# CM0_Controller.net
KiCad netlist of a schematic drawn in Altium Designer
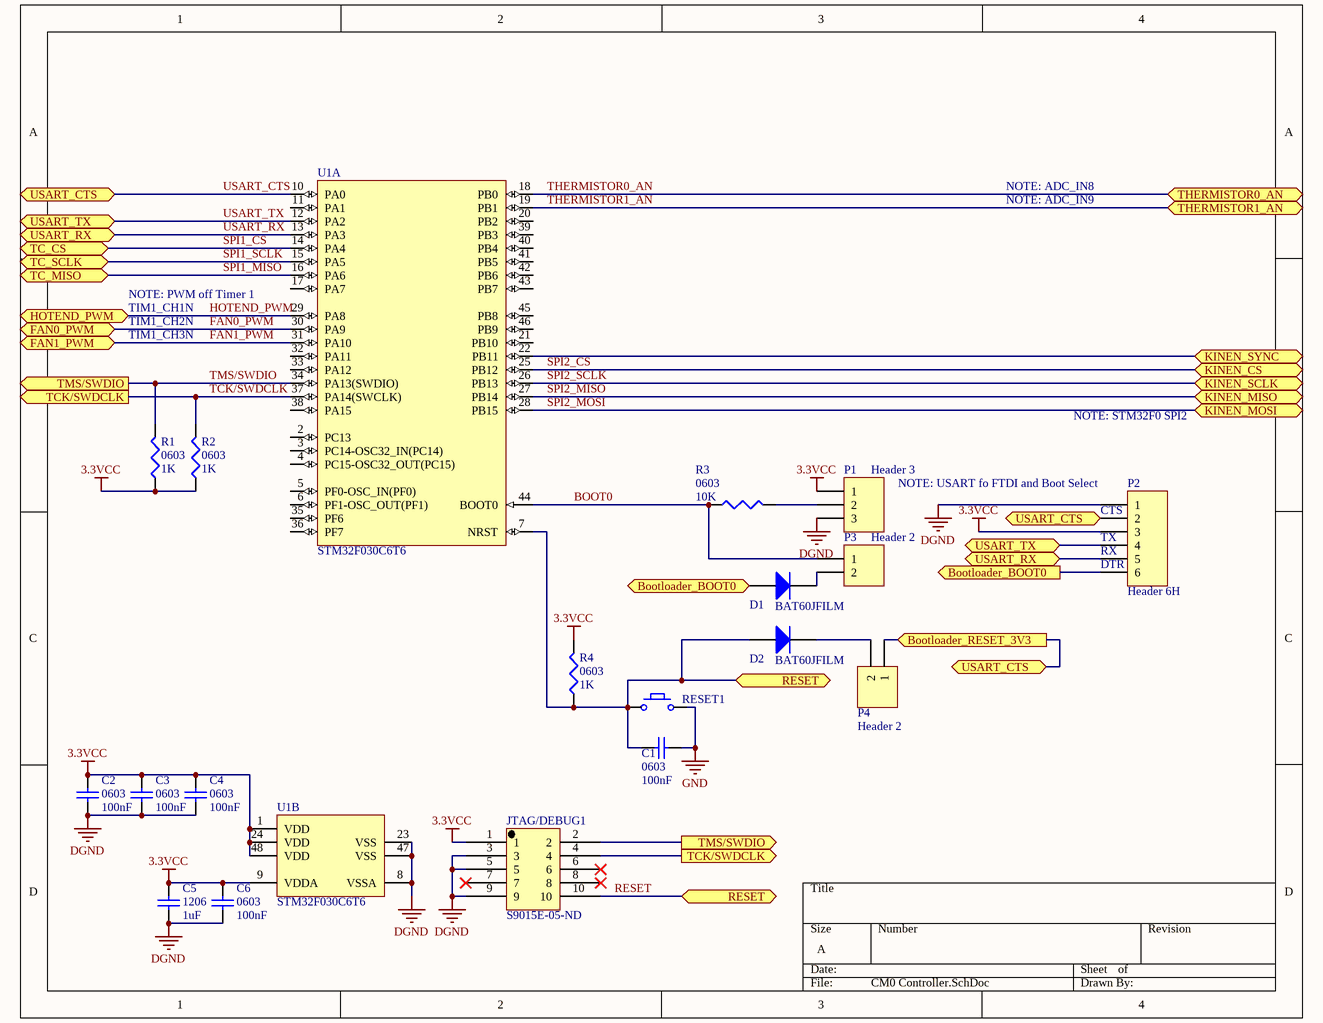
[diagram p0: CM0 Controller.SchDoc]

(export (version "E")
  (design (tool "Eeschema 10.0.6"))
  (components
    (comp (ref "C1")
      (value "0603")
      (footprint "1608[0603]")
      (description "Capacitor (Semiconductor SIM Model)")
      (fields (field (name "ALTIUM_VALUE") "100nF") (field (name "PUBLISHER") "Altium Limited"))
      (libsource (lib "Miscellaneous Devices") (part "Cap Semi"))
    )
    (comp (ref "C2")
      (value "0603")
      (footprint "1608[0603]")
      (description "Capacitor (Semiconductor SIM Model)")
      (fields (field (name "ALTIUM_VALUE") "100nF") (field (name "PUBLISHER") "Altium Limited"))
      (libsource (lib "Miscellaneous Devices") (part "Cap Semi"))
    )
    (comp (ref "C3")
      (value "0603")
      (footprint "1608[0603]")
      (description "Capacitor (Semiconductor SIM Model)")
      (fields (field (name "ALTIUM_VALUE") "100nF") (field (name "PUBLISHER") "Altium Limited"))
      (libsource (lib "Miscellaneous Devices") (part "Cap Semi"))
    )
    (comp (ref "C4")
      (value "0603")
      (footprint "1608[0603]")
      (description "Capacitor (Semiconductor SIM Model)")
      (fields (field (name "ALTIUM_VALUE") "100nF") (field (name "PUBLISHER") "Altium Limited"))
      (libsource (lib "Miscellaneous Devices") (part "Cap Semi"))
    )
    (comp (ref "C5")
      (value "1206")
      (footprint "C1206")
      (description "Capacitor (Semiconductor SIM Model)")
      (fields (field (name "ALTIUM_VALUE") "1uF") (field (name "PUBLISHER") "Altium Limited"))
      (libsource (lib "Miscellaneous Devices") (part "Cap Semi"))
    )
    (comp (ref "C6")
      (value "0603")
      (footprint "1608[0603]")
      (description "Capacitor (Semiconductor SIM Model)")
      (fields (field (name "ALTIUM_VALUE") "100nF") (field (name "PUBLISHER") "Altium Limited"))
      (libsource (lib "Miscellaneous Devices") (part "Cap Semi"))
    )
    (comp (ref "D1")
      (value "BAT60JFILM")
      (footprint "SOD-323")
      (description "Default Diode")
      (fields (field (name "PUBLISHER") "Altium Limited"))
      (libsource (lib "Miscellaneous Devices") (part "Diode"))
    )
    (comp (ref "D2")
      (value "BAT60JFILM")
      (footprint "SOD-323")
      (description "Default Diode")
      (fields (field (name "PUBLISHER") "Altium Limited"))
      (libsource (lib "Miscellaneous Devices") (part "Diode"))
    )
    (comp (ref "JTAG/DEBUG1")
      (value "S9015E-05-ND")
      (footprint "S9015E-05-ND")
      (libsource (lib "Adams Altium Library") (part "S9015E-05-ND"))
    )
    (comp (ref "P1")
      (value "Header 3")
      (footprint "HDR1X3")
      (description "Header, 3-Pin")
      (fields (field (name "PUBLISHER") "Altium Limited"))
      (libsource (lib "Miscellaneous Connectors") (part "Header 3"))
    )
    (comp (ref "P2")
      (value "Header 6H")
      (footprint "HDR1X6H")
      (description "Header, 6-Pin, Right Angle")
      (fields (field (name "PUBLISHER") "Altium Limited"))
      (libsource (lib "Miscellaneous Connectors") (part "Header 6H"))
    )
    (comp (ref "P3")
      (value "Header 2")
      (footprint "HDR1X2")
      (description "Header, 2-Pin")
      (fields (field (name "PUBLISHER") "Altium Limited"))
      (libsource (lib "") (part "Header 2_1"))
    )
    (comp (ref "P4")
      (value "Header 2")
      (footprint "HDR1X2")
      (description "Header, 2-Pin")
      (fields (field (name "PUBLISHER") "Altium Limited"))
      (libsource (lib "Miscellaneous Connectors") (part "Header 2"))
    )
    (comp (ref "R1")
      (value "0603")
      (footprint "J1-0603")
      (description "Resistor")
      (fields (field (name "ALTIUM_VALUE") "1K") (field (name "PUBLISHER") "Altium Limited"))
      (libsource (lib "Miscellaneous Devices") (part "Res3"))
    )
    (comp (ref "R2")
      (value "0603")
      (footprint "J1-0603")
      (description "Resistor")
      (fields (field (name "ALTIUM_VALUE") "1K") (field (name "PUBLISHER") "Altium Limited"))
      (libsource (lib "Miscellaneous Devices") (part "Res3"))
    )
    (comp (ref "R3")
      (value "0603")
      (footprint "J1-0603")
      (description "Resistor")
      (fields (field (name "ALTIUM_VALUE") "10K") (field (name "PUBLISHER") "Altium Limited"))
      (libsource (lib "Miscellaneous Devices") (part "Res3"))
    )
    (comp (ref "R4")
      (value "0603")
      (footprint "J1-0603")
      (description "Resistor")
      (fields (field (name "ALTIUM_VALUE") "1K") (field (name "PUBLISHER") "Altium Limited"))
      (libsource (lib "Miscellaneous Devices") (part "Res3"))
    )
    (comp (ref "RESET1")
      (value "Tactile Switch")
      (footprint "tactile switch")
      (libsource (lib "Adams Altium Library") (part "Tactile Switch"))
    )
    (comp (ref "U1")
      (value "STM32F030C6T6")
      (footprint "STM-LQFP48_L")
      (libsource (lib "STMicroelectronics STM32 F0") (part "STM32F030C6T6"))
    )
  )
  (nets
    (net (code "1") (name "/BOOT0") (class "Default")
      (node (ref "P3") (pin "1") (pinfunction "1_1") (pintype "passive"))
      (node (ref "R3") (pin "1") (pinfunction "1_1") (pintype "passive"))
      (node (ref "U1") (pin "44") (pinfunction "BOOT0_44") (pintype "input"))
    )
    (net (code "2") (name "/Bootloader_BOOT0") (class "Default")
      (node (ref "D1") (pin "1") (pinfunction "A_1") (pintype "passive"))
      (node (ref "P2") (pin "6") (pinfunction "6_6") (pintype "passive"))
    )
    (net (code "3") (name "/FAN0_PWM") (class "Default")
      (node (ref "U1") (pin "30") (pinfunction "PA9_30") (pintype "bidirectional"))
    )
    (net (code "4") (name "/FAN1_PWM") (class "Default")
      (node (ref "U1") (pin "31") (pinfunction "PA10_31") (pintype "bidirectional"))
    )
    (net (code "5") (name "/HOTEND_PWM") (class "Default")
      (node (ref "U1") (pin "29") (pinfunction "PA8_29") (pintype "bidirectional"))
    )
    (net (code "6") (name "/KINEN_SYNC") (class "Default")
      (node (ref "U1") (pin "22") (pinfunction "PB11_22") (pintype "bidirectional"))
    )
    (net (code "7") (name "/RESET") (class "Default")
      (node (ref "C1") (pin "2") (pinfunction "2_2") (pintype "passive"))
      (node (ref "D2") (pin "1") (pinfunction "A_1") (pintype "passive"))
      (node (ref "JTAG/DEBUG1") (pin "10") (pinfunction "10_10") (pintype "passive"))
      (node (ref "R4") (pin "1") (pinfunction "1_1") (pintype "passive"))
      (node (ref "RESET1") (pin "1") (pintype "passive"))
      (node (ref "U1") (pin "7") (pinfunction "NRST_7") (pintype "bidirectional"))
    )
    (net (code "8") (name "/SPI1_CS") (class "Default")
      (node (ref "U1") (pin "14") (pinfunction "PA4_14") (pintype "bidirectional"))
    )
    (net (code "9") (name "/SPI1_MISO") (class "Default")
      (node (ref "U1") (pin "16") (pinfunction "PA6_16") (pintype "bidirectional"))
    )
    (net (code "10") (name "/SPI1_SCLK") (class "Default")
      (node (ref "U1") (pin "15") (pinfunction "PA5_15") (pintype "bidirectional"))
    )
    (net (code "11") (name "/SPI2_CS") (class "Default")
      (node (ref "U1") (pin "25") (pinfunction "PB12_25") (pintype "bidirectional"))
    )
    (net (code "12") (name "/SPI2_MISO") (class "Default")
      (node (ref "U1") (pin "27") (pinfunction "PB14_27") (pintype "bidirectional"))
    )
    (net (code "13") (name "/SPI2_MOSI") (class "Default")
      (node (ref "U1") (pin "28") (pinfunction "PB15_28") (pintype "bidirectional"))
    )
    (net (code "14") (name "/SPI2_SCLK") (class "Default")
      (node (ref "U1") (pin "26") (pinfunction "PB13_26") (pintype "bidirectional"))
    )
    (net (code "15") (name "/TCK{slash}SWDCLK") (class "Default")
      (node (ref "JTAG/DEBUG1") (pin "4") (pinfunction "4_4") (pintype "passive"))
      (node (ref "R2") (pin "2") (pinfunction "2_2") (pintype "passive"))
      (node (ref "U1") (pin "37") (pinfunction "PA14(SWCLK)_37") (pintype "bidirectional"))
    )
    (net (code "16") (name "/THERMISTOR0_AN") (class "Default")
      (node (ref "U1") (pin "18") (pinfunction "PB0_18") (pintype "bidirectional"))
    )
    (net (code "17") (name "/THERMISTOR1_AN") (class "Default")
      (node (ref "U1") (pin "19") (pinfunction "PB1_19") (pintype "bidirectional"))
    )
    (net (code "18") (name "/TMS{slash}SWDIO") (class "Default")
      (node (ref "JTAG/DEBUG1") (pin "2") (pinfunction "2_2") (pintype "passive"))
      (node (ref "R1") (pin "2") (pinfunction "2_2") (pintype "passive"))
      (node (ref "U1") (pin "34") (pinfunction "PA13(SWDIO)_34") (pintype "bidirectional"))
    )
    (net (code "19") (name "/USART_CTS") (class "Default")
      (node (ref "P2") (pin "2") (pinfunction "2_2") (pintype "passive"))
      (node (ref "P4") (pin "1") (pinfunction "1_1") (pintype "passive"))
      (node (ref "U1") (pin "10") (pinfunction "PA0_10") (pintype "bidirectional"))
    )
    (net (code "20") (name "/USART_RX") (class "Default")
      (node (ref "P2") (pin "5") (pinfunction "5_5") (pintype "passive"))
      (node (ref "U1") (pin "13") (pinfunction "PA3_13") (pintype "bidirectional"))
    )
    (net (code "21") (name "/USART_TX") (class "Default")
      (node (ref "P2") (pin "4") (pinfunction "4_4") (pintype "passive"))
      (node (ref "U1") (pin "12") (pinfunction "PA2_12") (pintype "bidirectional"))
    )
    (net (code "22") (name "3.3VCC") (class "Default")
      (node (ref "C2") (pin "2") (pinfunction "2_2") (pintype "passive"))
      (node (ref "C3") (pin "2") (pinfunction "2_2") (pintype "passive"))
      (node (ref "C4") (pin "2") (pinfunction "2_2") (pintype "passive"))
      (node (ref "C5") (pin "1") (pinfunction "1_1") (pintype "passive"))
      (node (ref "C6") (pin "1") (pinfunction "1_1") (pintype "passive"))
      (node (ref "JTAG/DEBUG1") (pin "1") (pinfunction "1_1") (pintype "passive"))
      (node (ref "P1") (pin "1") (pinfunction "1_1") (pintype "passive"))
      (node (ref "P2") (pin "3") (pinfunction "3_3") (pintype "passive"))
      (node (ref "R1") (pin "1") (pinfunction "1_1") (pintype "passive"))
      (node (ref "R2") (pin "1") (pinfunction "1_1") (pintype "passive"))
      (node (ref "R4") (pin "2") (pinfunction "2_2") (pintype "passive"))
      (node (ref "U1") (pin "1") (pinfunction "VDD_1") (pintype "power_in"))
      (node (ref "U1") (pin "24") (pinfunction "VDD_24") (pintype "power_in"))
      (node (ref "U1") (pin "48") (pinfunction "VDD_48") (pintype "power_in"))
      (node (ref "U1") (pin "9") (pinfunction "VDDA_9") (pintype "power_in"))
    )
    (net (code "23") (name "DGND") (class "Default")
      (node (ref "C2") (pin "1") (pinfunction "1_1") (pintype "passive"))
      (node (ref "C3") (pin "1") (pinfunction "1_1") (pintype "passive"))
      (node (ref "C4") (pin "1") (pinfunction "1_1") (pintype "passive"))
      (node (ref "C5") (pin "2") (pinfunction "2_2") (pintype "passive"))
      (node (ref "C6") (pin "2") (pinfunction "2_2") (pintype "passive"))
      (node (ref "JTAG/DEBUG1") (pin "3") (pinfunction "3_3") (pintype "passive"))
      (node (ref "JTAG/DEBUG1") (pin "5") (pinfunction "5_5") (pintype "passive"))
      (node (ref "JTAG/DEBUG1") (pin "9") (pinfunction "9_9") (pintype "passive"))
      (node (ref "P1") (pin "3") (pinfunction "3_3") (pintype "passive"))
      (node (ref "P2") (pin "1") (pinfunction "1_1") (pintype "passive"))
      (node (ref "U1") (pin "23") (pinfunction "VSS_23") (pintype "power_in"))
      (node (ref "U1") (pin "47") (pinfunction "VSS_47") (pintype "power_in"))
      (node (ref "U1") (pin "8") (pinfunction "VSSA_8") (pintype "power_in"))
    )
    (net (code "24") (name "GND") (class "Default")
      (node (ref "C1") (pin "1") (pinfunction "1_1") (pintype "passive"))
      (node (ref "RESET1") (pin "2") (pintype "passive"))
    )
    (net (code "25") (name "Net-(D1-K)") (class "Default")
      (node (ref "D1") (pin "2") (pinfunction "K_2") (pintype "passive"))
      (node (ref "P3") (pin "2") (pinfunction "2_2") (pintype "passive"))
    )
    (net (code "26") (name "Net-(D2-K)") (class "Default")
      (node (ref "D2") (pin "2") (pinfunction "K_2") (pintype "passive"))
      (node (ref "P4") (pin "2") (pinfunction "2_2") (pintype "passive"))
    )
    (net (code "27") (name "Net-(P1-Pad2)") (class "Default")
      (node (ref "P1") (pin "2") (pinfunction "2_2") (pintype "passive"))
      (node (ref "R3") (pin "2") (pinfunction "2_2") (pintype "passive"))
    )
    (net (code "28") (name "unconnected-(JTAG/DEBUG1-Pad6)") (class "Default")
      (node (ref "JTAG/DEBUG1") (pin "6") (pinfunction "6_6") (pintype "passive+no_connect"))
    )
    (net (code "29") (name "unconnected-(JTAG/DEBUG1-Pad7)") (class "Default")
      (node (ref "JTAG/DEBUG1") (pin "7") (pinfunction "7_7") (pintype "passive+no_connect"))
    )
    (net (code "30") (name "unconnected-(JTAG/DEBUG1-Pad8)") (class "Default")
      (node (ref "JTAG/DEBUG1") (pin "8") (pinfunction "8_8") (pintype "passive+no_connect"))
    )
    (net (code "31") (name "unconnected-(U1A-PA1-Pad11)") (class "Default")
      (node (ref "U1") (pin "11") (pinfunction "PA1_11") (pintype "bidirectional"))
    )
    (net (code "32") (name "unconnected-(U1A-PA7-Pad17)") (class "Default")
      (node (ref "U1") (pin "17") (pinfunction "PA7_17") (pintype "bidirectional"))
    )
    (net (code "33") (name "unconnected-(U1A-PA11-Pad32)") (class "Default")
      (node (ref "U1") (pin "32") (pinfunction "PA11_32") (pintype "bidirectional"))
    )
    (net (code "34") (name "unconnected-(U1A-PA12-Pad33)") (class "Default")
      (node (ref "U1") (pin "33") (pinfunction "PA12_33") (pintype "bidirectional"))
    )
    (net (code "35") (name "unconnected-(U1A-PA15-Pad38)") (class "Default")
      (node (ref "U1") (pin "38") (pinfunction "PA15_38") (pintype "bidirectional"))
    )
    (net (code "36") (name "unconnected-(U1A-PB2-Pad20)") (class "Default")
      (node (ref "U1") (pin "20") (pinfunction "PB2_20") (pintype "bidirectional"))
    )
    (net (code "37") (name "unconnected-(U1A-PB3-Pad39)") (class "Default")
      (node (ref "U1") (pin "39") (pinfunction "PB3_39") (pintype "bidirectional"))
    )
    (net (code "38") (name "unconnected-(U1A-PB4-Pad40)") (class "Default")
      (node (ref "U1") (pin "40") (pinfunction "PB4_40") (pintype "bidirectional"))
    )
    (net (code "39") (name "unconnected-(U1A-PB5-Pad41)") (class "Default")
      (node (ref "U1") (pin "41") (pinfunction "PB5_41") (pintype "bidirectional"))
    )
    (net (code "40") (name "unconnected-(U1A-PB6-Pad42)") (class "Default")
      (node (ref "U1") (pin "42") (pinfunction "PB6_42") (pintype "bidirectional"))
    )
    (net (code "41") (name "unconnected-(U1A-PB7-Pad43)") (class "Default")
      (node (ref "U1") (pin "43") (pinfunction "PB7_43") (pintype "bidirectional"))
    )
    (net (code "42") (name "unconnected-(U1A-PB8-Pad45)") (class "Default")
      (node (ref "U1") (pin "45") (pinfunction "PB8_45") (pintype "bidirectional"))
    )
    (net (code "43") (name "unconnected-(U1A-PB9-Pad46)") (class "Default")
      (node (ref "U1") (pin "46") (pinfunction "PB9_46") (pintype "bidirectional"))
    )
    (net (code "44") (name "unconnected-(U1A-PB10-Pad21)") (class "Default")
      (node (ref "U1") (pin "21") (pinfunction "PB10_21") (pintype "bidirectional"))
    )
    (net (code "45") (name "unconnected-(U1A-PC13-Pad2)") (class "Default")
      (node (ref "U1") (pin "2") (pinfunction "PC13_2") (pintype "bidirectional"))
    )
    (net (code "46") (name "unconnected-(U1A-PC14-OSC32_IN(PC14)-Pad3)") (class "Default")
      (node (ref "U1") (pin "3") (pinfunction "PC14-OSC32_IN(PC14)_3") (pintype "bidirectional"))
    )
    (net (code "47") (name "unconnected-(U1A-PC15-OSC32_OUT(PC15)-Pad4)") (class "Default")
      (node (ref "U1") (pin "4") (pinfunction "PC15-OSC32_OUT(PC15)_4") (pintype "bidirectional"))
    )
    (net (code "48") (name "unconnected-(U1A-PF0-OSC_IN(PF0)-Pad5)") (class "Default")
      (node (ref "U1") (pin "5") (pinfunction "PF0-OSC_IN(PF0)_5") (pintype "bidirectional"))
    )
    (net (code "49") (name "unconnected-(U1A-PF1-OSC_OUT(PF1)-Pad6)") (class "Default")
      (node (ref "U1") (pin "6") (pinfunction "PF1-OSC_OUT(PF1)_6") (pintype "bidirectional"))
    )
    (net (code "50") (name "unconnected-(U1A-PF6-Pad35)") (class "Default")
      (node (ref "U1") (pin "35") (pinfunction "PF6_35") (pintype "bidirectional"))
    )
    (net (code "51") (name "unconnected-(U1A-PF7-Pad36)") (class "Default")
      (node (ref "U1") (pin "36") (pinfunction "PF7_36") (pintype "bidirectional"))
    )
  )
)
